# FabScan-Shield_v11.net
KiCad netlist of a schematic drawn in EAGLE
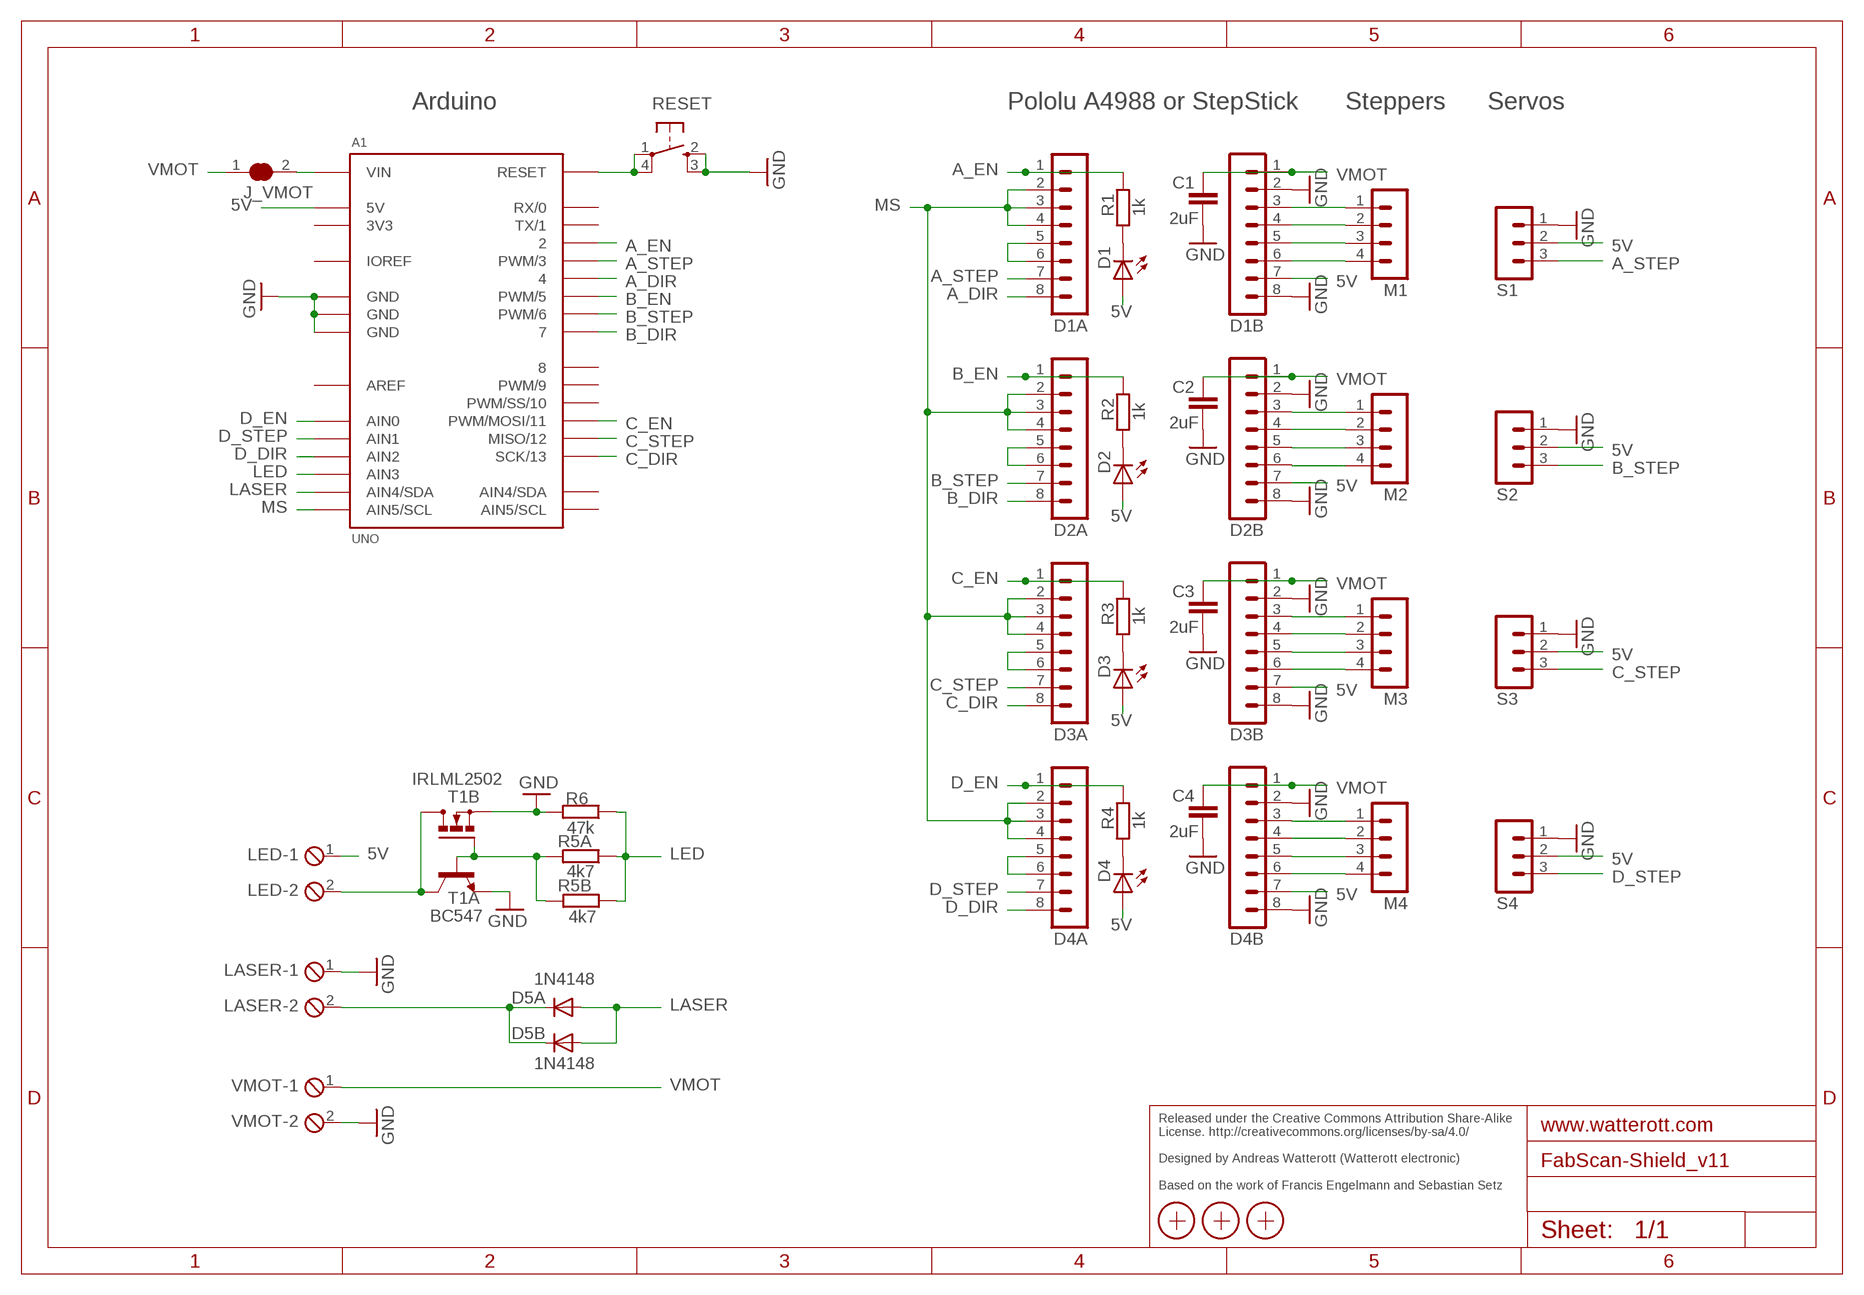
[diagram p0: schematic, sheet 1]

(export (version "E")
  (design (tool "Eeschema 10.0.6"))
  (components
    (comp (ref "A1")
      (value "UNO")
      (footprint "eagle-import:UNO")
      (libsource (lib "eagle-import") (part "UNO"))
    )
    (comp (ref "C1")
      (value "2uF")
      (footprint "eagle-import:C0603")
      (libsource (lib "eagle-import") (part "C-EUC0603"))
    )
    (comp (ref "C2")
      (value "2uF")
      (footprint "eagle-import:C0603")
      (libsource (lib "eagle-import") (part "C-EUC0603"))
    )
    (comp (ref "C3")
      (value "2uF")
      (footprint "eagle-import:C0603")
      (libsource (lib "eagle-import") (part "C-EUC0603"))
    )
    (comp (ref "C4")
      (value "2uF")
      (footprint "eagle-import:C0603")
      (libsource (lib "eagle-import") (part "C-EUC0603"))
    )
    (comp (ref "D1")
      (value "LEDCHIPLED_0603")
      (footprint "eagle-import:CHIPLED_0603")
      (libsource (lib "eagle-import") (part "LEDCHIPLED_0603"))
    )
    (comp (ref "D1A")
      (value "MA08-1")
      (footprint "eagle-import:MA08-1")
      (libsource (lib "eagle-import") (part "MA08-1"))
    )
    (comp (ref "D1B")
      (value "MA08-1")
      (footprint "eagle-import:MA08-1")
      (libsource (lib "eagle-import") (part "MA08-1"))
    )
    (comp (ref "D2")
      (value "LEDCHIPLED_0603")
      (footprint "eagle-import:CHIPLED_0603")
      (libsource (lib "eagle-import") (part "LEDCHIPLED_0603"))
    )
    (comp (ref "D2A")
      (value "MA08-1")
      (footprint "eagle-import:MA08-1")
      (libsource (lib "eagle-import") (part "MA08-1"))
    )
    (comp (ref "D2B")
      (value "MA08-1")
      (footprint "eagle-import:MA08-1")
      (libsource (lib "eagle-import") (part "MA08-1"))
    )
    (comp (ref "D3")
      (value "LEDCHIPLED_0603")
      (footprint "eagle-import:CHIPLED_0603")
      (libsource (lib "eagle-import") (part "LEDCHIPLED_0603"))
    )
    (comp (ref "D3A")
      (value "MA08-1")
      (footprint "eagle-import:MA08-1")
      (libsource (lib "eagle-import") (part "MA08-1"))
    )
    (comp (ref "D3B")
      (value "MA08-1")
      (footprint "eagle-import:MA08-1")
      (libsource (lib "eagle-import") (part "MA08-1"))
    )
    (comp (ref "D4")
      (value "LEDCHIPLED_0603")
      (footprint "eagle-import:CHIPLED_0603")
      (libsource (lib "eagle-import") (part "LEDCHIPLED_0603"))
    )
    (comp (ref "D4A")
      (value "MA08-1")
      (footprint "eagle-import:MA08-1")
      (libsource (lib "eagle-import") (part "MA08-1"))
    )
    (comp (ref "D4B")
      (value "MA08-1")
      (footprint "eagle-import:MA08-1")
      (libsource (lib "eagle-import") (part "MA08-1"))
    )
    (comp (ref "D5A")
      (value "1N4148")
      (footprint "eagle-import:DO35-7")
      (libsource (lib "eagle-import") (part "1N4148DO35-7"))
    )
    (comp (ref "D5B")
      (value "1N4148")
      (footprint "eagle-import:SOD106-R")
      (libsource (lib "eagle-import") (part "DIODE-SOD106-R"))
    )
    (comp (ref "J_VMOT")
      (value "SJ")
      (footprint "eagle-import:SJ")
      (libsource (lib "eagle-import") (part "SJ"))
    )
    (comp (ref "LASER")
      (value "MPT2")
      (footprint "eagle-import:2POL254")
      (fields (field (name "OC_FARNELL") "unknown") (field (name "OC_NEWARK") "unknown"))
      (libsource (lib "eagle-import") (part "MPT2"))
    )
    (comp (ref "LED")
      (value "MPT2")
      (footprint "eagle-import:2POL254")
      (libsource (lib "eagle-import") (part "MPT2"))
    )
    (comp (ref "M1")
      (value "MA04-1")
      (footprint "eagle-import:MA04-1")
      (libsource (lib "eagle-import") (part "MA04-1"))
    )
    (comp (ref "M2")
      (value "MA04-1")
      (footprint "eagle-import:MA04-1")
      (fields (field (name "OC_FARNELL") "unknown") (field (name "OC_NEWARK") "unknown"))
      (libsource (lib "eagle-import") (part "MA04-1"))
    )
    (comp (ref "M3")
      (value "MA04-1")
      (footprint "eagle-import:MA04-1")
      (fields (field (name "OC_FARNELL") "unknown") (field (name "OC_NEWARK") "unknown"))
      (libsource (lib "eagle-import") (part "MA04-1"))
    )
    (comp (ref "M4")
      (value "MA04-1")
      (footprint "eagle-import:MA04-1")
      (fields (field (name "OC_FARNELL") "unknown") (field (name "OC_NEWARK") "unknown"))
      (libsource (lib "eagle-import") (part "MA04-1"))
    )
    (comp (ref "R1")
      (value "1k")
      (footprint "eagle-import:R0603")
      (libsource (lib "eagle-import") (part "R-EU_R0603"))
    )
    (comp (ref "R2")
      (value "1k")
      (footprint "eagle-import:R0603")
      (libsource (lib "eagle-import") (part "R-EU_R0603"))
    )
    (comp (ref "R3")
      (value "1k")
      (footprint "eagle-import:R0603")
      (libsource (lib "eagle-import") (part "R-EU_R0603"))
    )
    (comp (ref "R4")
      (value "1k")
      (footprint "eagle-import:R0603")
      (libsource (lib "eagle-import") (part "R-EU_R0603"))
    )
    (comp (ref "R5A")
      (value "4k7")
      (footprint "eagle-import:0204_7")
      (libsource (lib "eagle-import") (part "R-EU_0204/7"))
    )
    (comp (ref "R5B")
      (value "4k7")
      (footprint "eagle-import:R0603")
      (libsource (lib "eagle-import") (part "R-EU_R0603"))
    )
    (comp (ref "R6")
      (value "47k")
      (footprint "eagle-import:R0603")
      (libsource (lib "eagle-import") (part "R-EU_R0603"))
    )
    (comp (ref "RESET")
      (value "SW_SMDS")
      (footprint "eagle-import:SW_SMD4")
      (libsource (lib "eagle-import") (part "SW_SMDS"))
    )
    (comp (ref "S1")
      (value "MA03-1")
      (footprint "eagle-import:MA03-1")
      (libsource (lib "eagle-import") (part "MA03-1"))
    )
    (comp (ref "S2")
      (value "MA03-1")
      (footprint "eagle-import:MA03-1")
      (libsource (lib "eagle-import") (part "MA03-1"))
    )
    (comp (ref "S3")
      (value "MA03-1")
      (footprint "eagle-import:MA03-1")
      (libsource (lib "eagle-import") (part "MA03-1"))
    )
    (comp (ref "S4")
      (value "MA03-1")
      (footprint "eagle-import:MA03-1")
      (libsource (lib "eagle-import") (part "MA03-1"))
    )
    (comp (ref "T1A")
      (value "BC547")
      (footprint "eagle-import:TO92")
      (libsource (lib "eagle-import") (part "BC547"))
    )
    (comp (ref "T1B")
      (value "IRLML2502")
      (footprint "eagle-import:MICRO3")
      (libsource (lib "eagle-import") (part "IRLML2502"))
    )
    (comp (ref "VMOT")
      (value "MPT2")
      (footprint "eagle-import:2POL254")
      (fields (field (name "OC_FARNELL") "unknown") (field (name "OC_NEWARK") "unknown"))
      (libsource (lib "eagle-import") (part "MPT2"))
    )
    (comp (ref "X1")
      (value "PASSER")
      (footprint "eagle-import:PASSER")
      (libsource (lib "eagle-import") (part "PASSER"))
    )
    (comp (ref "X2")
      (value "PASSER")
      (footprint "eagle-import:PASSER")
      (libsource (lib "eagle-import") (part "PASSER"))
    )
    (comp (ref "X3")
      (value "PASSER")
      (footprint "eagle-import:PASSER")
      (libsource (lib "eagle-import") (part "PASSER"))
    )
  )
  (nets
    (net (code "1") (name "/3V3") (class "Default")
      (node (ref "A1") (pin "3V3") (pinfunction "3V3_3V3") (pintype "power_in"))
    )
    (net (code "2") (name "/5V") (class "Default")
      (node (ref "A1") (pin "5V") (pinfunction "5V_5V") (pintype "power_in"))
      (node (ref "D1") (pin "A") (pinfunction "A_A") (pintype "passive"))
      (node (ref "D1B") (pin "7") (pinfunction "7_7") (pintype "passive"))
      (node (ref "D2") (pin "A") (pinfunction "A_A") (pintype "passive"))
      (node (ref "D2B") (pin "7") (pinfunction "7_7") (pintype "passive"))
      (node (ref "D3") (pin "A") (pinfunction "A_A") (pintype "passive"))
      (node (ref "D3B") (pin "7") (pinfunction "7_7") (pintype "passive"))
      (node (ref "D4") (pin "A") (pinfunction "A_A") (pintype "passive"))
      (node (ref "D4B") (pin "7") (pinfunction "7_7") (pintype "passive"))
      (node (ref "LED") (pin "1") (pinfunction "1_1") (pintype "passive"))
      (node (ref "S1") (pin "2") (pinfunction "2_2") (pintype "passive"))
      (node (ref "S2") (pin "2") (pinfunction "2_2") (pintype "passive"))
      (node (ref "S3") (pin "2") (pinfunction "2_2") (pintype "passive"))
      (node (ref "S4") (pin "2") (pinfunction "2_2") (pintype "passive"))
    )
    (net (code "3") (name "/AREF") (class "Default")
      (node (ref "A1") (pin "AREF") (pinfunction "AREF_AREF") (pintype "power_in"))
    )
    (net (code "4") (name "/A_DIR") (class "Default")
      (node (ref "A1") (pin "4") (pinfunction "4_4") (pintype "bidirectional"))
      (node (ref "D1A") (pin "8") (pinfunction "8_8") (pintype "passive"))
    )
    (net (code "5") (name "/A_EN") (class "Default")
      (node (ref "A1") (pin "2") (pinfunction "2_2") (pintype "bidirectional"))
      (node (ref "D1A") (pin "1") (pinfunction "1_1") (pintype "passive"))
      (node (ref "R1") (pin "1") (pinfunction "1_1") (pintype "passive"))
    )
    (net (code "6") (name "/A_STEP") (class "Default")
      (node (ref "A1") (pin "3") (pinfunction "PWM/3_3") (pintype "bidirectional"))
      (node (ref "D1A") (pin "7") (pinfunction "7_7") (pintype "passive"))
      (node (ref "S1") (pin "3") (pinfunction "3_3") (pintype "passive"))
    )
    (net (code "7") (name "/B_DIR") (class "Default")
      (node (ref "A1") (pin "7") (pinfunction "7_7") (pintype "bidirectional"))
      (node (ref "D2A") (pin "8") (pinfunction "8_8") (pintype "passive"))
    )
    (net (code "8") (name "/B_EN") (class "Default")
      (node (ref "A1") (pin "5") (pinfunction "PWM/5_5") (pintype "bidirectional"))
      (node (ref "D2A") (pin "1") (pinfunction "1_1") (pintype "passive"))
      (node (ref "R2") (pin "1") (pinfunction "1_1") (pintype "passive"))
    )
    (net (code "9") (name "/B_STEP") (class "Default")
      (node (ref "A1") (pin "6") (pinfunction "PWM/6_6") (pintype "bidirectional"))
      (node (ref "D2A") (pin "7") (pinfunction "7_7") (pintype "passive"))
      (node (ref "S2") (pin "3") (pinfunction "3_3") (pintype "passive"))
    )
    (net (code "10") (name "/C_DIR") (class "Default")
      (node (ref "A1") (pin "13") (pinfunction "SCK/13_13") (pintype "bidirectional"))
      (node (ref "D3A") (pin "8") (pinfunction "8_8") (pintype "passive"))
    )
    (net (code "11") (name "/C_EN") (class "Default")
      (node (ref "A1") (pin "11") (pinfunction "PWM/MOSI/11_11") (pintype "bidirectional"))
      (node (ref "D3A") (pin "1") (pinfunction "1_1") (pintype "passive"))
      (node (ref "R3") (pin "1") (pinfunction "1_1") (pintype "passive"))
    )
    (net (code "12") (name "/C_STEP") (class "Default")
      (node (ref "A1") (pin "12") (pinfunction "MISO/12_12") (pintype "bidirectional"))
      (node (ref "D3A") (pin "7") (pinfunction "7_7") (pintype "passive"))
      (node (ref "S3") (pin "3") (pinfunction "3_3") (pintype "passive"))
    )
    (net (code "13") (name "/D_DIR") (class "Default")
      (node (ref "A1") (pin "AIN2") (pinfunction "AIN2_AIN2") (pintype "bidirectional"))
      (node (ref "D4A") (pin "8") (pinfunction "8_8") (pintype "passive"))
    )
    (net (code "14") (name "/D_EN") (class "Default")
      (node (ref "A1") (pin "AIN0") (pinfunction "AIN0_AIN0") (pintype "bidirectional"))
      (node (ref "D4A") (pin "1") (pinfunction "1_1") (pintype "passive"))
      (node (ref "R4") (pin "1") (pinfunction "1_1") (pintype "passive"))
    )
    (net (code "15") (name "/D_STEP") (class "Default")
      (node (ref "A1") (pin "AIN1") (pinfunction "AIN1_AIN1") (pintype "bidirectional"))
      (node (ref "D4A") (pin "7") (pinfunction "7_7") (pintype "passive"))
      (node (ref "S4") (pin "3") (pinfunction "3_3") (pintype "passive"))
    )
    (net (code "16") (name "/IOREF") (class "Default")
      (node (ref "A1") (pin "IOREF") (pinfunction "IOREF_IOREF") (pintype "power_in"))
    )
    (net (code "17") (name "/LASER") (class "Default")
      (node (ref "A1") (pin "AIN4") (pinfunction "AIN4/SDA_AIN4") (pintype "bidirectional"))
      (node (ref "D5A") (pin "A") (pinfunction "A_A") (pintype "passive"))
      (node (ref "D5B") (pin "A") (pinfunction "A_A") (pintype "passive"))
    )
    (net (code "18") (name "/LED") (class "Default")
      (node (ref "A1") (pin "AIN3") (pinfunction "AIN3_AIN3") (pintype "bidirectional"))
      (node (ref "R5A") (pin "1") (pinfunction "1_1") (pintype "passive"))
      (node (ref "R5B") (pin "2") (pinfunction "2_2") (pintype "passive"))
      (node (ref "R6") (pin "1") (pinfunction "1_1") (pintype "passive"))
    )
    (net (code "19") (name "/MS") (class "Default")
      (node (ref "A1") (pin "AIN5") (pinfunction "AIN5/SCL_AIN5") (pintype "bidirectional"))
      (node (ref "D1A") (pin "2") (pinfunction "2_2") (pintype "passive"))
      (node (ref "D1A") (pin "3") (pinfunction "3_3") (pintype "passive"))
      (node (ref "D1A") (pin "4") (pinfunction "4_4") (pintype "passive"))
      (node (ref "D2A") (pin "2") (pinfunction "2_2") (pintype "passive"))
      (node (ref "D2A") (pin "3") (pinfunction "3_3") (pintype "passive"))
      (node (ref "D2A") (pin "4") (pinfunction "4_4") (pintype "passive"))
      (node (ref "D3A") (pin "2") (pinfunction "2_2") (pintype "passive"))
      (node (ref "D3A") (pin "3") (pinfunction "3_3") (pintype "passive"))
      (node (ref "D3A") (pin "4") (pinfunction "4_4") (pintype "passive"))
      (node (ref "D4A") (pin "2") (pinfunction "2_2") (pintype "passive"))
      (node (ref "D4A") (pin "3") (pinfunction "3_3") (pintype "passive"))
      (node (ref "D4A") (pin "4") (pinfunction "4_4") (pintype "passive"))
    )
    (net (code "20") (name "/VMOT") (class "Default")
      (node (ref "C1") (pin "1") (pinfunction "1_1") (pintype "passive"))
      (node (ref "C2") (pin "1") (pinfunction "1_1") (pintype "passive"))
      (node (ref "C3") (pin "1") (pinfunction "1_1") (pintype "passive"))
      (node (ref "C4") (pin "1") (pinfunction "1_1") (pintype "passive"))
      (node (ref "D1B") (pin "1") (pinfunction "1_1") (pintype "passive"))
      (node (ref "D2B") (pin "1") (pinfunction "1_1") (pintype "passive"))
      (node (ref "D3B") (pin "1") (pinfunction "1_1") (pintype "passive"))
      (node (ref "D4B") (pin "1") (pinfunction "1_1") (pintype "passive"))
      (node (ref "J_VMOT") (pin "1") (pinfunction "1_1") (pintype "passive"))
      (node (ref "VMOT") (pin "1") (pinfunction "1_1") (pintype "passive"))
    )
    (net (code "21") (name "GND") (class "Default")
      (node (ref "A1") (pin "GND@1") (pinfunction "GND_GND@1") (pintype "power_in"))
      (node (ref "A1") (pin "GND@2") (pinfunction "GND_GND@2") (pintype "power_in"))
      (node (ref "A1") (pin "GND@3") (pinfunction "GND_GND@3") (pintype "power_in"))
      (node (ref "C1") (pin "2") (pinfunction "2_2") (pintype "passive"))
      (node (ref "C2") (pin "2") (pinfunction "2_2") (pintype "passive"))
      (node (ref "C3") (pin "2") (pinfunction "2_2") (pintype "passive"))
      (node (ref "C4") (pin "2") (pinfunction "2_2") (pintype "passive"))
      (node (ref "D1B") (pin "2") (pinfunction "2_2") (pintype "passive"))
      (node (ref "D1B") (pin "8") (pinfunction "8_8") (pintype "passive"))
      (node (ref "D2B") (pin "2") (pinfunction "2_2") (pintype "passive"))
      (node (ref "D2B") (pin "8") (pinfunction "8_8") (pintype "passive"))
      (node (ref "D3B") (pin "2") (pinfunction "2_2") (pintype "passive"))
      (node (ref "D3B") (pin "8") (pinfunction "8_8") (pintype "passive"))
      (node (ref "D4B") (pin "2") (pinfunction "2_2") (pintype "passive"))
      (node (ref "D4B") (pin "8") (pinfunction "8_8") (pintype "passive"))
      (node (ref "LASER") (pin "1") (pinfunction "1_1") (pintype "passive"))
      (node (ref "R6") (pin "2") (pinfunction "2_2") (pintype "passive"))
      (node (ref "RESET") (pin "2") (pinfunction "S_2") (pintype "passive"))
      (node (ref "RESET") (pin "3") (pinfunction "S1_3") (pintype "passive"))
      (node (ref "S1") (pin "1") (pinfunction "1_1") (pintype "passive"))
      (node (ref "S2") (pin "1") (pinfunction "1_1") (pintype "passive"))
      (node (ref "S3") (pin "1") (pinfunction "1_1") (pintype "passive"))
      (node (ref "S4") (pin "1") (pinfunction "1_1") (pintype "passive"))
      (node (ref "T1A") (pin "1") (pinfunction "E_1") (pintype "passive"))
      (node (ref "T1B") (pin "2") (pinfunction "S_2") (pintype "passive"))
      (node (ref "VMOT") (pin "2") (pinfunction "1_2") (pintype "passive"))
    )
    (net (code "22") (name "Net-(A1-PadVIN)") (class "Default")
      (node (ref "A1") (pin "VIN") (pinfunction "VIN_VIN") (pintype "power_in"))
      (node (ref "J_VMOT") (pin "2") (pinfunction "2_2") (pintype "passive"))
    )
    (net (code "23") (name "Net-(A1-RESET)") (class "Default")
      (node (ref "A1") (pin "RST") (pinfunction "RESET_RST") (pintype "bidirectional"))
      (node (ref "RESET") (pin "1") (pinfunction "P_1") (pintype "passive"))
      (node (ref "RESET") (pin "4") (pinfunction "P1_4") (pintype "passive"))
    )
    (net (code "24") (name "Net-(D1-PadC)") (class "Default")
      (node (ref "D1") (pin "C") (pinfunction "C_C") (pintype "passive"))
      (node (ref "R1") (pin "2") (pinfunction "2_2") (pintype "passive"))
    )
    (net (code "25") (name "Net-(D1A-Pad5)") (class "Default")
      (node (ref "D1A") (pin "5") (pinfunction "5_5") (pintype "passive"))
      (node (ref "D1A") (pin "6") (pinfunction "6_6") (pintype "passive"))
    )
    (net (code "26") (name "Net-(D1B-Pad3)") (class "Default")
      (node (ref "D1B") (pin "3") (pinfunction "3_3") (pintype "passive"))
      (node (ref "M1") (pin "1") (pinfunction "1_1") (pintype "passive"))
    )
    (net (code "27") (name "Net-(D1B-Pad4)") (class "Default")
      (node (ref "D1B") (pin "4") (pinfunction "4_4") (pintype "passive"))
      (node (ref "M1") (pin "2") (pinfunction "2_2") (pintype "passive"))
    )
    (net (code "28") (name "Net-(D1B-Pad5)") (class "Default")
      (node (ref "D1B") (pin "5") (pinfunction "5_5") (pintype "passive"))
      (node (ref "M1") (pin "3") (pinfunction "3_3") (pintype "passive"))
    )
    (net (code "29") (name "Net-(D1B-Pad6)") (class "Default")
      (node (ref "D1B") (pin "6") (pinfunction "6_6") (pintype "passive"))
      (node (ref "M1") (pin "4") (pinfunction "4_4") (pintype "passive"))
    )
    (net (code "30") (name "Net-(D2-PadC)") (class "Default")
      (node (ref "D2") (pin "C") (pinfunction "C_C") (pintype "passive"))
      (node (ref "R2") (pin "2") (pinfunction "2_2") (pintype "passive"))
    )
    (net (code "31") (name "Net-(D2A-Pad5)") (class "Default")
      (node (ref "D2A") (pin "5") (pinfunction "5_5") (pintype "passive"))
      (node (ref "D2A") (pin "6") (pinfunction "6_6") (pintype "passive"))
    )
    (net (code "32") (name "Net-(D2B-Pad3)") (class "Default")
      (node (ref "D2B") (pin "3") (pinfunction "3_3") (pintype "passive"))
      (node (ref "M2") (pin "1") (pinfunction "1_1") (pintype "passive"))
    )
    (net (code "33") (name "Net-(D2B-Pad4)") (class "Default")
      (node (ref "D2B") (pin "4") (pinfunction "4_4") (pintype "passive"))
      (node (ref "M2") (pin "2") (pinfunction "2_2") (pintype "passive"))
    )
    (net (code "34") (name "Net-(D2B-Pad5)") (class "Default")
      (node (ref "D2B") (pin "5") (pinfunction "5_5") (pintype "passive"))
      (node (ref "M2") (pin "3") (pinfunction "3_3") (pintype "passive"))
    )
    (net (code "35") (name "Net-(D2B-Pad6)") (class "Default")
      (node (ref "D2B") (pin "6") (pinfunction "6_6") (pintype "passive"))
      (node (ref "M2") (pin "4") (pinfunction "4_4") (pintype "passive"))
    )
    (net (code "36") (name "Net-(D3-PadC)") (class "Default")
      (node (ref "D3") (pin "C") (pinfunction "C_C") (pintype "passive"))
      (node (ref "R3") (pin "2") (pinfunction "2_2") (pintype "passive"))
    )
    (net (code "37") (name "Net-(D3A-Pad5)") (class "Default")
      (node (ref "D3A") (pin "5") (pinfunction "5_5") (pintype "passive"))
      (node (ref "D3A") (pin "6") (pinfunction "6_6") (pintype "passive"))
    )
    (net (code "38") (name "Net-(D3B-Pad3)") (class "Default")
      (node (ref "D3B") (pin "3") (pinfunction "3_3") (pintype "passive"))
      (node (ref "M3") (pin "1") (pinfunction "1_1") (pintype "passive"))
    )
    (net (code "39") (name "Net-(D3B-Pad4)") (class "Default")
      (node (ref "D3B") (pin "4") (pinfunction "4_4") (pintype "passive"))
      (node (ref "M3") (pin "2") (pinfunction "2_2") (pintype "passive"))
    )
    (net (code "40") (name "Net-(D3B-Pad5)") (class "Default")
      (node (ref "D3B") (pin "5") (pinfunction "5_5") (pintype "passive"))
      (node (ref "M3") (pin "3") (pinfunction "3_3") (pintype "passive"))
    )
    (net (code "41") (name "Net-(D3B-Pad6)") (class "Default")
      (node (ref "D3B") (pin "6") (pinfunction "6_6") (pintype "passive"))
      (node (ref "M3") (pin "4") (pinfunction "4_4") (pintype "passive"))
    )
    (net (code "42") (name "Net-(D4-PadC)") (class "Default")
      (node (ref "D4") (pin "C") (pinfunction "C_C") (pintype "passive"))
      (node (ref "R4") (pin "2") (pinfunction "2_2") (pintype "passive"))
    )
    (net (code "43") (name "Net-(D4A-Pad5)") (class "Default")
      (node (ref "D4A") (pin "5") (pinfunction "5_5") (pintype "passive"))
      (node (ref "D4A") (pin "6") (pinfunction "6_6") (pintype "passive"))
    )
    (net (code "44") (name "Net-(D4B-Pad3)") (class "Default")
      (node (ref "D4B") (pin "3") (pinfunction "3_3") (pintype "passive"))
      (node (ref "M4") (pin "1") (pinfunction "1_1") (pintype "passive"))
    )
    (net (code "45") (name "Net-(D4B-Pad4)") (class "Default")
      (node (ref "D4B") (pin "4") (pinfunction "4_4") (pintype "passive"))
      (node (ref "M4") (pin "2") (pinfunction "2_2") (pintype "passive"))
    )
    (net (code "46") (name "Net-(D4B-Pad5)") (class "Default")
      (node (ref "D4B") (pin "5") (pinfunction "5_5") (pintype "passive"))
      (node (ref "M4") (pin "3") (pinfunction "3_3") (pintype "passive"))
    )
    (net (code "47") (name "Net-(D4B-Pad6)") (class "Default")
      (node (ref "D4B") (pin "6") (pinfunction "6_6") (pintype "passive"))
      (node (ref "M4") (pin "4") (pinfunction "4_4") (pintype "passive"))
    )
    (net (code "48") (name "Net-(LASERB-1)") (class "Default")
      (node (ref "D5A") (pin "C") (pinfunction "C_C") (pintype "passive"))
      (node (ref "D5B") (pin "C") (pinfunction "C_C") (pintype "passive"))
      (node (ref "LASER") (pin "2") (pinfunction "1_2") (pintype "passive"))
    )
    (net (code "49") (name "Net-(LEDB-1)") (class "Default")
      (node (ref "LED") (pin "2") (pinfunction "1_2") (pintype "passive"))
      (node (ref "T1A") (pin "3") (pinfunction "C_3") (pintype "passive"))
      (node (ref "T1B") (pin "3") (pinfunction "D_3") (pintype "passive"))
    )
    (net (code "50") (name "Net-(T1A-B)") (class "Default")
      (node (ref "R5A") (pin "2") (pinfunction "2_2") (pintype "passive"))
      (node (ref "R5B") (pin "1") (pinfunction "1_1") (pintype "passive"))
      (node (ref "T1A") (pin "2") (pinfunction "B_2") (pintype "passive"))
      (node (ref "T1B") (pin "1") (pinfunction "G_1") (pintype "passive"))
    )
    (net (code "51") (name "unconnected-(A1-AIN4{slash}SDA-PadSDA)") (class "Default")
      (node (ref "A1") (pin "SDA") (pinfunction "AIN4/SDA_SDA") (pintype "bidirectional"))
    )
    (net (code "52") (name "unconnected-(A1-AIN5{slash}SCL-PadSCL)") (class "Default")
      (node (ref "A1") (pin "SCL") (pinfunction "AIN5/SCL_SCL") (pintype "bidirectional"))
    )
    (net (code "53") (name "unconnected-(A1-PWM{slash}9-Pad9)") (class "Default")
      (node (ref "A1") (pin "9") (pinfunction "PWM/9_9") (pintype "bidirectional"))
    )
    (net (code "54") (name "unconnected-(A1-PWM{slash}SS{slash}10-Pad10)") (class "Default")
      (node (ref "A1") (pin "10") (pinfunction "PWM/SS/10_10") (pintype "bidirectional"))
    )
    (net (code "55") (name "unconnected-(A1-Pad8)") (class "Default")
      (node (ref "A1") (pin "8") (pinfunction "8_8") (pintype "bidirectional"))
    )
    (net (code "56") (name "unconnected-(A1-RX{slash}0-Pad0)") (class "Default")
      (node (ref "A1") (pin "0") (pinfunction "RX/0_0") (pintype "bidirectional"))
    )
    (net (code "57") (name "unconnected-(A1-TX{slash}1-Pad1)") (class "Default")
      (node (ref "A1") (pin "1") (pinfunction "TX/1_1") (pintype "bidirectional"))
    )
  )
)
